# 03_Power.net
KiCad netlist of a schematic drawn in Altium Designer
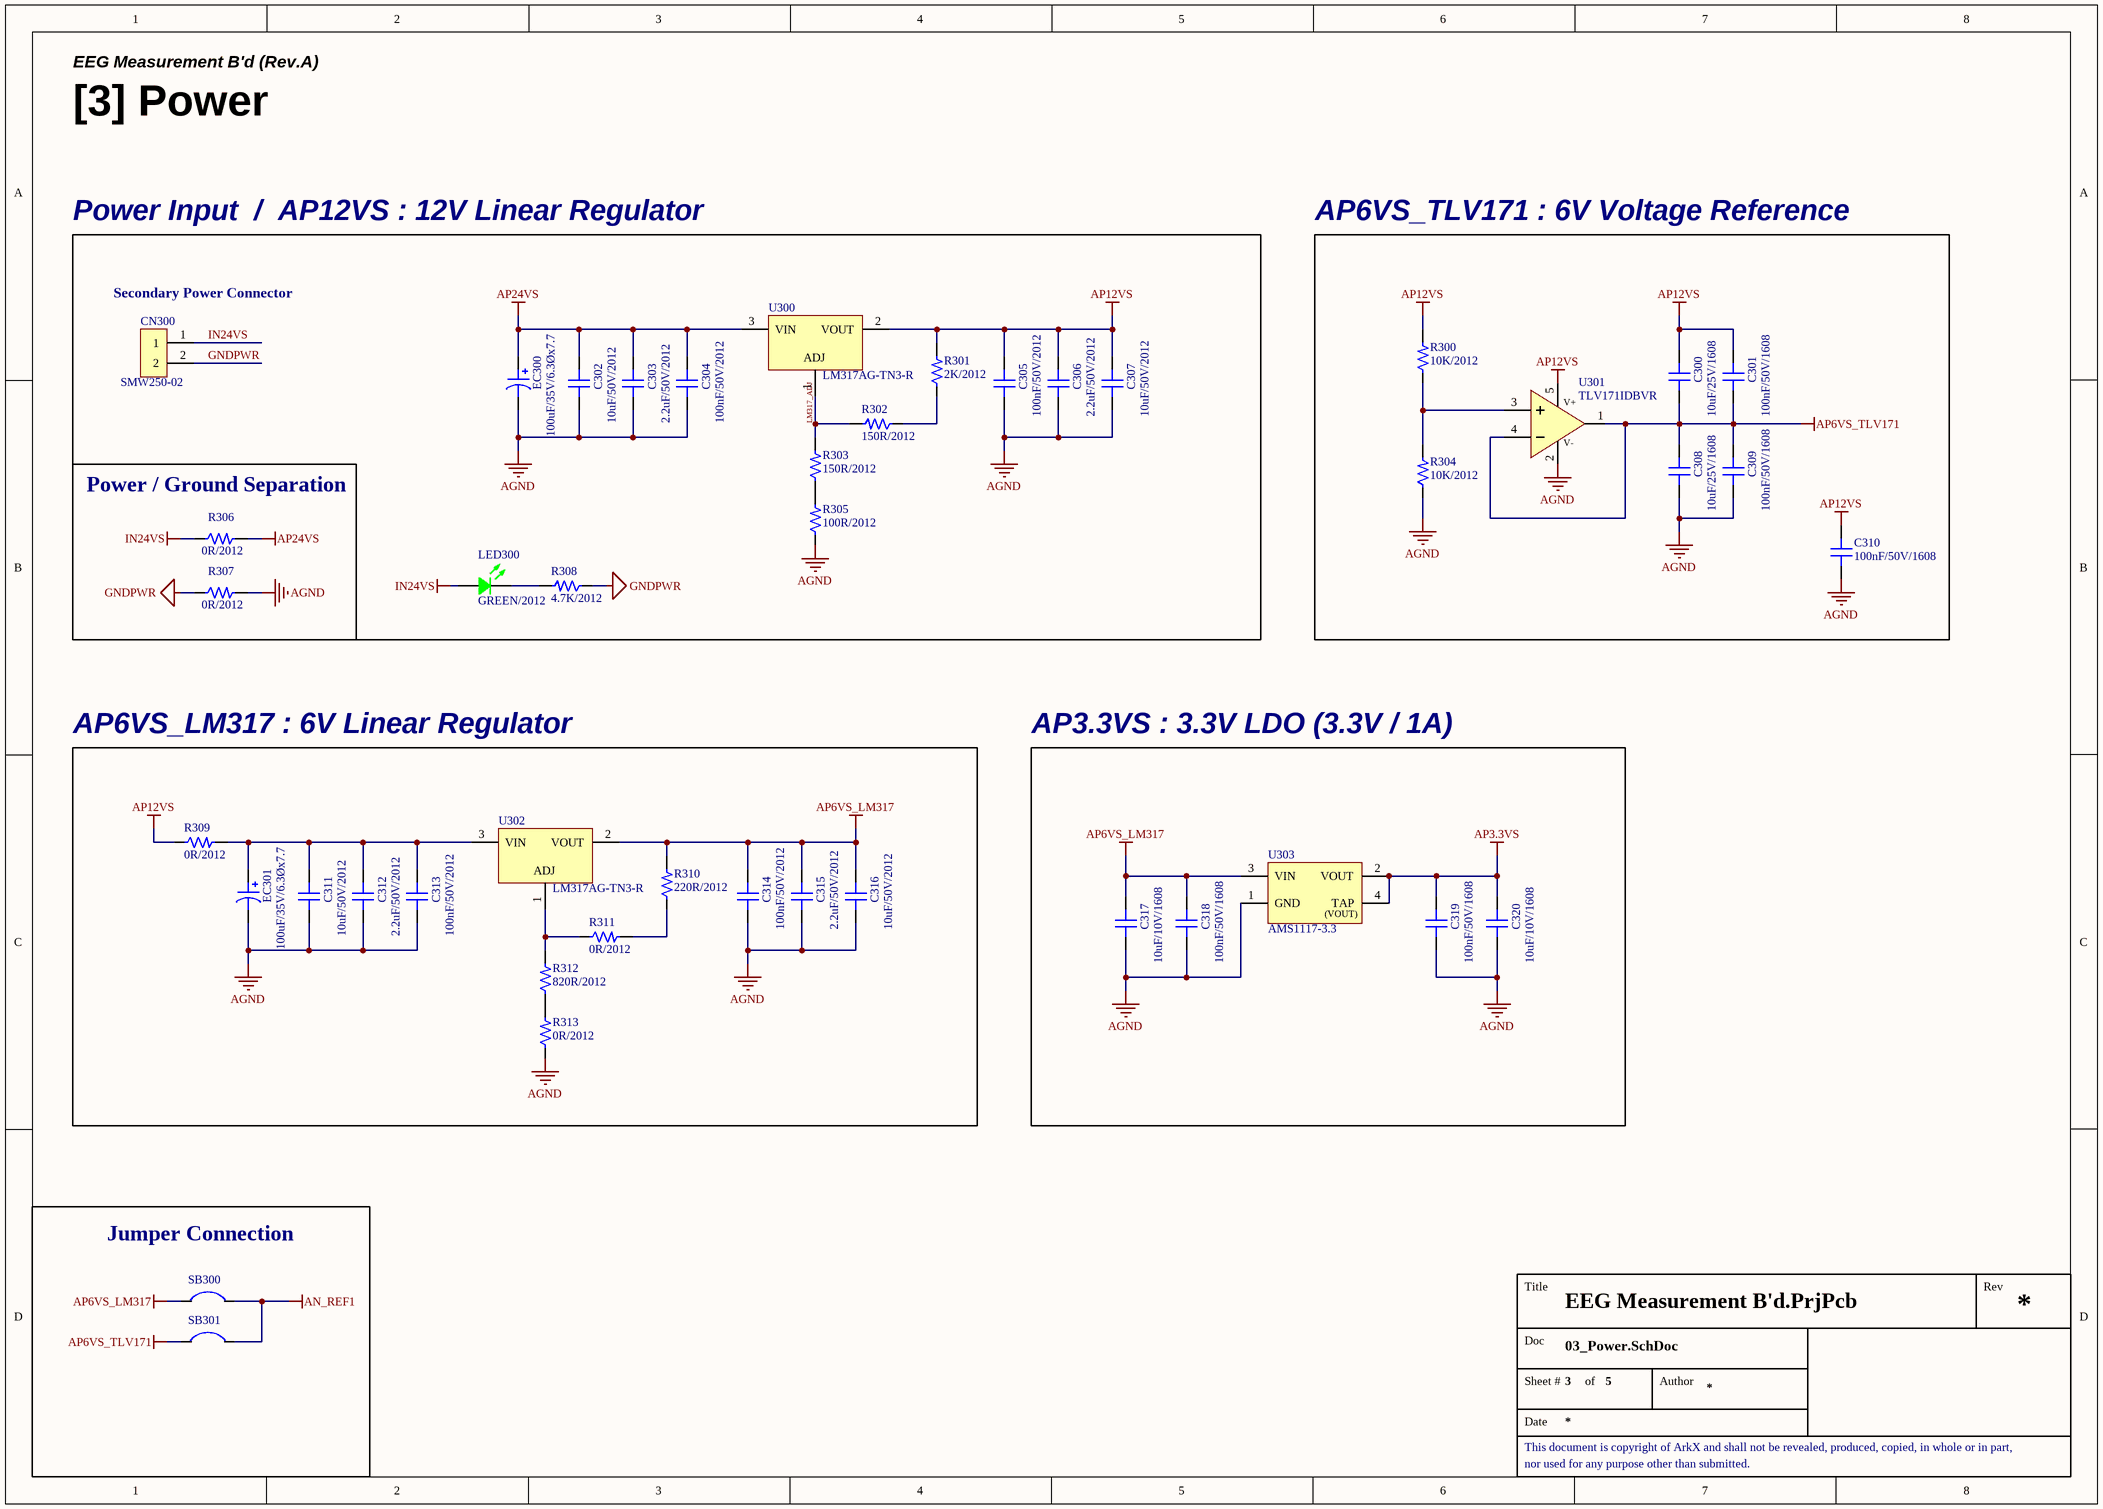
[diagram p0: 03_Power.SchDoc]

(export (version "E")
  (design (tool "Eeschema 10.0.6"))
  (components
    (comp (ref "C300")
      (value "10uF/25V/1608")
      (footprint "CAP 1608 (0603_INCH)")
      (description "Ceramic CAP_10uF/25V/1608")
      (fields (field (name "LCSC PART #") "C96446"))
      (libsource (lib "Arkx") (part "CAP_10uF/25V/1608"))
    )
    (comp (ref "C301")
      (value "100nF/50V/1608")
      (footprint "CAP 1608 (0603_INCH)")
      (description "Ceramic CAP_100nF/50V/1608")
      (fields (field (name "LCSC PART #") "C14663"))
      (libsource (lib "Arkx") (part "CAP_100nF/50V/1608"))
    )
    (comp (ref "C302")
      (value "10uF/50V/2012")
      (footprint "CAP 2012 (0805_INCH)")
      (description "Ceramic CAP_10uF/50V/2012")
      (fields (field (name "LCSC PART #") "C440198"))
      (libsource (lib "Arkx") (part "CAP_10uF/50V/2012"))
    )
    (comp (ref "C303")
      (value "2.2uF/50V/2012")
      (footprint "CAP 2012 (0805_INCH)")
      (description "Ceramic CAP_2.2uF/50V/2012")
      (fields (field (name "LCSC PART #") "C377773"))
      (libsource (lib "Arkx") (part "CAP_2.2uF/50V/2012"))
    )
    (comp (ref "C304")
      (value "100nF/50V/2012")
      (footprint "CAP 2012 (0805_INCH)")
      (description "Ceramic CAP_100nF/50V/2012")
      (fields (field (name "LCSC PART #") "C49678"))
      (libsource (lib "Arkx") (part "CAP_100nF/50V/2012"))
    )
    (comp (ref "C305")
      (value "100nF/50V/2012")
      (footprint "CAP 2012 (0805_INCH)")
      (description "Ceramic CAP_100nF/50V/2012")
      (fields (field (name "LCSC PART #") "C49678"))
      (libsource (lib "Arkx") (part "CAP_100nF/50V/2012"))
    )
    (comp (ref "C306")
      (value "2.2uF/50V/2012")
      (footprint "CAP 2012 (0805_INCH)")
      (description "Ceramic CAP_2.2uF/50V/2012")
      (fields (field (name "LCSC PART #") "C377773"))
      (libsource (lib "Arkx") (part "CAP_2.2uF/50V/2012"))
    )
    (comp (ref "C307")
      (value "10uF/50V/2012")
      (footprint "CAP 2012 (0805_INCH)")
      (description "Ceramic CAP_10uF/50V/2012")
      (fields (field (name "LCSC PART #") "C440198"))
      (libsource (lib "Arkx") (part "CAP_10uF/50V/2012"))
    )
    (comp (ref "C308")
      (value "10uF/25V/1608")
      (footprint "CAP 1608 (0603_INCH)")
      (description "Ceramic CAP_10uF/25V/1608")
      (fields (field (name "LCSC PART #") "C96446"))
      (libsource (lib "Arkx") (part "CAP_10uF/25V/1608"))
    )
    (comp (ref "C309")
      (value "100nF/50V/1608")
      (footprint "CAP 1608 (0603_INCH)")
      (description "Ceramic CAP_100nF/50V/1608")
      (fields (field (name "LCSC PART #") "C14663"))
      (libsource (lib "Arkx") (part "CAP_100nF/50V/1608"))
    )
    (comp (ref "C310")
      (value "100nF/50V/1608")
      (footprint "CAP 1608 (0603_INCH)")
      (description "Ceramic CAP_100nF/50V/1608")
      (fields (field (name "LCSC PART #") "C14663"))
      (libsource (lib "Arkx") (part "CAP_100nF/50V/1608"))
    )
    (comp (ref "C311")
      (value "10uF/50V/2012")
      (footprint "CAP 2012 (0805_INCH)")
      (description "Ceramic CAP_10uF/50V/2012")
      (fields (field (name "LCSC PART #") "C440198"))
      (libsource (lib "Arkx") (part "CAP_10uF/50V/2012"))
    )
    (comp (ref "C312")
      (value "2.2uF/50V/2012")
      (footprint "CAP 2012 (0805_INCH)")
      (description "Ceramic CAP_2.2uF/50V/2012")
      (fields (field (name "LCSC PART #") "C377773"))
      (libsource (lib "Arkx") (part "CAP_2.2uF/50V/2012"))
    )
    (comp (ref "C313")
      (value "100nF/50V/2012")
      (footprint "CAP 2012 (0805_INCH)")
      (description "Ceramic CAP_100nF/50V/2012")
      (fields (field (name "LCSC PART #") "C49678"))
      (libsource (lib "Arkx") (part "CAP_100nF/50V/2012"))
    )
    (comp (ref "C314")
      (value "100nF/50V/2012")
      (footprint "CAP 2012 (0805_INCH)")
      (description "Ceramic CAP_100nF/50V/2012")
      (fields (field (name "LCSC PART #") "C49678"))
      (libsource (lib "Arkx") (part "CAP_100nF/50V/2012"))
    )
    (comp (ref "C315")
      (value "2.2uF/50V/2012")
      (footprint "CAP 2012 (0805_INCH)")
      (description "Ceramic CAP_2.2uF/50V/2012")
      (fields (field (name "LCSC PART #") "C377773"))
      (libsource (lib "Arkx") (part "CAP_2.2uF/50V/2012"))
    )
    (comp (ref "C316")
      (value "10uF/50V/2012")
      (footprint "CAP 2012 (0805_INCH)")
      (description "Ceramic CAP_10uF/50V/2012")
      (fields (field (name "LCSC PART #") "C440198"))
      (libsource (lib "Arkx") (part "CAP_10uF/50V/2012"))
    )
    (comp (ref "C317")
      (value "10uF/10V/1608")
      (footprint "CAP 1608 (0603_INCH)")
      (description "Ceramic CAP_10uF/10V/1608")
      (fields (field (name "LCSC PART #") "C19702"))
      (libsource (lib "Arkx") (part "CAP_10uF/10V/1608"))
    )
    (comp (ref "C318")
      (value "100nF/50V/1608")
      (footprint "CAP 1608 (0603_INCH)")
      (description "Ceramic CAP_100nF/50V/1608")
      (fields (field (name "LCSC PART #") "C14663"))
      (libsource (lib "Arkx") (part "CAP_100nF/50V/1608"))
    )
    (comp (ref "C319")
      (value "100nF/50V/1608")
      (footprint "CAP 1608 (0603_INCH)")
      (description "Ceramic CAP_100nF/50V/1608")
      (fields (field (name "LCSC PART #") "C14663"))
      (libsource (lib "Arkx") (part "CAP_100nF/50V/1608"))
    )
    (comp (ref "C320")
      (value "10uF/10V/1608")
      (footprint "CAP 1608 (0603_INCH)")
      (description "Ceramic CAP_10uF/10V/1608")
      (fields (field (name "LCSC PART #") "C19702"))
      (libsource (lib "Arkx") (part "CAP_10uF/10V/1608"))
    )
    (comp (ref "CN300")
      (value "SMW250-02")
      (footprint "CON_SMW250-02")
      (description "YEONHO 2.5mm Pitch Vertical Connector 2Pin")
      (libsource (lib "Arkx") (part "CON_SMW250-02"))
    )
    (comp (ref "EC300")
      (value "100uF/35V/6.3Øx7.7")
      (footprint "CAP ALSMD 6.6MM H7.7MM")
      (description "Eletrolytic CAP_100uF/35V/6.3Øx7.7")
      (fields (field (name "LCSC PART #") "C176666"))
      (libsource (lib "Arkx") (part "CAP_EC 100uF/35V/6.3Øx7.7"))
    )
    (comp (ref "EC301")
      (value "100uF/35V/6.3Øx7.7")
      (footprint "CAP ALSMD 6.6MM H7.7MM")
      (description "Eletrolytic CAP_100uF/35V/6.3Øx7.7")
      (fields (field (name "LCSC PART #") "C176666"))
      (libsource (lib "Arkx") (part "CAP_EC 100uF/35V/6.3Øx7.7"))
    )
    (comp (ref "LED300")
      (value "GREEN/2012")
      (footprint "LED MHT170RGBCT (GREEN)")
      (fields (field (name "LCSC PART #") "C2962094"))
      (libsource (lib "Arkx") (part "LED_MHT170RGBCT(GREEN)"))
    )
    (comp (ref "R300")
      (value "10K/2012")
      (footprint "RES 2012 (0805_inch)")
      (description "RES_10K/2012/0.125W")
      (fields (field (name "LCSC PART #") "C17414"))
      (libsource (lib "Arkx") (part "RES_10K/2012/0.125W"))
    )
    (comp (ref "R301")
      (value "2K/2012")
      (footprint "RES 2012 (0805_inch)")
      (description "RES_2K/2012/0.125W")
      (fields (field (name "LCSC PART #") "C17604"))
      (libsource (lib "Arkx") (part "RES_2K/2012/0.125W"))
    )
    (comp (ref "R302")
      (value "150R/2012")
      (footprint "RES 2012 (0805_inch)")
      (description "RES_150R/2012/0.125W")
      (fields (field (name "LCSC PART #") "C17471"))
      (libsource (lib "Arkx") (part "RES_150R/2012/0.125W"))
    )
    (comp (ref "R303")
      (value "150R/2012")
      (footprint "RES 2012 (0805_inch)")
      (description "RES_150R/2012/0.125W")
      (fields (field (name "LCSC PART #") "C17471"))
      (libsource (lib "Arkx") (part "RES_150R/2012/0.125W"))
    )
    (comp (ref "R304")
      (value "10K/2012")
      (footprint "RES 2012 (0805_inch)")
      (description "RES_10K/2012/0.125W")
      (fields (field (name "LCSC PART #") "C17414"))
      (libsource (lib "Arkx") (part "RES_10K/2012/0.125W"))
    )
    (comp (ref "R305")
      (value "100R/2012")
      (footprint "RES 2012 (0805_inch)")
      (description "RES_100R/2012/0.125W")
      (fields (field (name "LCSC PART #") "C17408"))
      (libsource (lib "Arkx") (part "RES_100R/2012/0.125W"))
    )
    (comp (ref "R306")
      (value "0R/2012")
      (footprint "RES 2012 (0805_inch)")
      (description "RES_0R/2012/0.125W")
      (fields (field (name "LCSC PART #") "C17477"))
      (libsource (lib "Arkx") (part "RES_0R/2012/0.125W"))
    )
    (comp (ref "R307")
      (value "0R/2012")
      (footprint "RES 2012 (0805_inch)")
      (description "RES_0R/2012/0.125W")
      (fields (field (name "LCSC PART #") "C17477"))
      (libsource (lib "Arkx") (part "RES_0R/2012/0.125W"))
    )
    (comp (ref "R308")
      (value "4.7K/2012")
      (footprint "RES 2012 (0805_inch)")
      (description "RES_4.7K/2012/0.125W")
      (fields (field (name "LCSC PART #") "C17673"))
      (libsource (lib "Arkx") (part "RES_4.7K/2012/0.125W"))
    )
    (comp (ref "R309")
      (value "0R/2012")
      (footprint "RES 2012 (0805_inch)")
      (description "RES_0R/2012/0.125W")
      (fields (field (name "LCSC PART #") "C17477"))
      (libsource (lib "Arkx") (part "RES_0R/2012/0.125W"))
    )
    (comp (ref "R310")
      (value "220R/2012")
      (footprint "RES 2012 (0805_inch)")
      (description "RES_220R/2012/0.125W")
      (fields (field (name "LCSC PART #") "C17557"))
      (libsource (lib "Arkx") (part "RES_220R/2012/0.125W"))
    )
    (comp (ref "R311")
      (value "0R/2012")
      (footprint "RES 2012 (0805_inch)")
      (description "RES_0R/2012/0.125W")
      (fields (field (name "LCSC PART #") "C17477"))
      (libsource (lib "Arkx") (part "RES_0R/2012/0.125W"))
    )
    (comp (ref "R312")
      (value "820R/2012")
      (footprint "RES 2012 (0805_inch)")
      (description "RES_820R/2012/0.125W")
      (fields (field (name "LCSC PART #") "C17837"))
      (libsource (lib "Arkx") (part "RES_820R/2012/0.125W"))
    )
    (comp (ref "R313")
      (value "0R/2012")
      (footprint "RES 2012 (0805_inch)")
      (description "RES_0R/2012/0.125W")
      (fields (field (name "LCSC PART #") "C17477"))
      (libsource (lib "Arkx") (part "RES_0R/2012/0.125W"))
    )
    (comp (ref "SB300")
      (value "SB")
      (footprint "SB (Solder-Bridge)")
      (description "SB_Solder-Bridge")
      (libsource (lib "Arkx") (part "SB_Solder-Bridge"))
    )
    (comp (ref "SB301")
      (value "SB")
      (footprint "SB (Solder-Bridge)")
      (description "SB_Solder-Bridge")
      (libsource (lib "Arkx") (part "SB_Solder-Bridge"))
    )
    (comp (ref "U300")
      (value "LM317AG-TN3-R")
      (footprint "IC_TO-252-2(DPAK)")
      (fields (field (name "LCSC PART #") "C75510"))
      (libsource (lib "Arkx") (part "IC_REG_LM317AG-TN3-R"))
    )
    (comp (ref "U301")
      (value "TLV171IDBVR")
      (footprint "SOT-23-5 (TI DBV PACKAGE)")
      (description "Single, 36-V, 3-MHz, low-power operational amplifier for cost-sensitive applications")
      (fields (field (name "LCSC PART #") "C2864299"))
      (libsource (lib "Arkx") (part "IC_OPAMP_TLV171IDBVR"))
    )
    (comp (ref "U302")
      (value "LM317AG-TN3-R")
      (footprint "IC_TO-252-2(DPAK)")
      (fields (field (name "LCSC PART #") "C75510"))
      (libsource (lib "Arkx") (part "IC_REG_LM317AG-TN3-R"))
    )
    (comp (ref "U303")
      (value "AMS1117-3.3")
      (footprint "SOT 223-3 (DIODES INCORPORATED)")
      (fields (field (name "LCSC PART #") "C6186"))
      (libsource (lib "Arkx") (part "IC_REG_AMS1117-3.3"))
    )
  )
  (nets
    (net (code "1") (name "/LM317_ADJ") (class "Default")
      (node (ref "R302") (pin "2") (pinfunction "2_2") (pintype "passive"))
      (node (ref "R303") (pin "2") (pinfunction "2_2") (pintype "passive"))
      (node (ref "U300") (pin "1") (pinfunction "ADJ_1") (pintype "passive"))
    )
    (net (code "2") (name "AGND") (class "Default")
      (node (ref "C302") (pin "1") (pinfunction "1_1") (pintype "passive"))
      (node (ref "C303") (pin "1") (pinfunction "1_1") (pintype "passive"))
      (node (ref "C304") (pin "1") (pinfunction "1_1") (pintype "passive"))
      (node (ref "C305") (pin "1") (pinfunction "1_1") (pintype "passive"))
      (node (ref "C306") (pin "1") (pinfunction "1_1") (pintype "passive"))
      (node (ref "C307") (pin "1") (pinfunction "1_1") (pintype "passive"))
      (node (ref "C308") (pin "1") (pinfunction "1_1") (pintype "passive"))
      (node (ref "C309") (pin "1") (pinfunction "1_1") (pintype "passive"))
      (node (ref "C310") (pin "1") (pinfunction "1_1") (pintype "passive"))
      (node (ref "C311") (pin "1") (pinfunction "1_1") (pintype "passive"))
      (node (ref "C312") (pin "1") (pinfunction "1_1") (pintype "passive"))
      (node (ref "C313") (pin "1") (pinfunction "1_1") (pintype "passive"))
      (node (ref "C314") (pin "1") (pinfunction "1_1") (pintype "passive"))
      (node (ref "C315") (pin "1") (pinfunction "1_1") (pintype "passive"))
      (node (ref "C316") (pin "1") (pinfunction "1_1") (pintype "passive"))
      (node (ref "C317") (pin "1") (pinfunction "1_1") (pintype "passive"))
      (node (ref "C318") (pin "1") (pinfunction "1_1") (pintype "passive"))
      (node (ref "C319") (pin "1") (pinfunction "1_1") (pintype "passive"))
      (node (ref "C320") (pin "1") (pinfunction "1_1") (pintype "passive"))
      (node (ref "EC300") (pin "2") (pinfunction "2_2") (pintype "passive"))
      (node (ref "EC301") (pin "2") (pinfunction "2_2") (pintype "passive"))
      (node (ref "R304") (pin "1") (pinfunction "1_1") (pintype "passive"))
      (node (ref "R305") (pin "1") (pinfunction "1_1") (pintype "passive"))
      (node (ref "R307") (pin "2") (pinfunction "2_2") (pintype "passive"))
      (node (ref "R313") (pin "1") (pinfunction "1_1") (pintype "passive"))
      (node (ref "U301") (pin "2") (pinfunction "V-_2") (pintype "passive"))
      (node (ref "U303") (pin "1") (pinfunction "GND_1") (pintype "passive"))
    )
    (net (code "3") (name "AN_REF1") (class "Default")
      (node (ref "SB300") (pin "1") (pinfunction "1_1") (pintype "passive"))
      (node (ref "SB301") (pin "1") (pinfunction "1_1") (pintype "passive"))
    )
    (net (code "4") (name "AP3.3VS") (class "Default")
      (node (ref "C319") (pin "2") (pinfunction "2_2") (pintype "passive"))
      (node (ref "C320") (pin "2") (pinfunction "2_2") (pintype "passive"))
      (node (ref "U303") (pin "2") (pinfunction "VOUT_2") (pintype "passive"))
      (node (ref "U303") (pin "4") (pinfunction "TAP_4") (pintype "passive"))
    )
    (net (code "5") (name "AP6VS_LM317") (class "Default")
      (node (ref "C314") (pin "2") (pinfunction "2_2") (pintype "passive"))
      (node (ref "C315") (pin "2") (pinfunction "2_2") (pintype "passive"))
      (node (ref "C316") (pin "2") (pinfunction "2_2") (pintype "passive"))
      (node (ref "C317") (pin "2") (pinfunction "2_2") (pintype "passive"))
      (node (ref "C318") (pin "2") (pinfunction "2_2") (pintype "passive"))
      (node (ref "R310") (pin "2") (pinfunction "2_2") (pintype "passive"))
      (node (ref "SB300") (pin "2") (pinfunction "2_2") (pintype "passive"))
      (node (ref "U302") (pin "2") (pinfunction "VOUT_2") (pintype "passive"))
      (node (ref "U303") (pin "3") (pinfunction "VIN_3") (pintype "passive"))
    )
    (net (code "6") (name "AP6VS_TLV171") (class "Default")
      (node (ref "C300") (pin "1") (pinfunction "1_1") (pintype "passive"))
      (node (ref "C301") (pin "1") (pinfunction "1_1") (pintype "passive"))
      (node (ref "C308") (pin "2") (pinfunction "2_2") (pintype "passive"))
      (node (ref "C309") (pin "2") (pinfunction "2_2") (pintype "passive"))
      (node (ref "SB301") (pin "2") (pinfunction "2_2") (pintype "passive"))
      (node (ref "U301") (pin "1") (pinfunction "OUT_1") (pintype "passive"))
      (node (ref "U301") (pin "4") (pinfunction "IN-_4") (pintype "passive"))
    )
    (net (code "7") (name "AP12VS") (class "Default")
      (node (ref "C300") (pin "2") (pinfunction "2_2") (pintype "passive"))
      (node (ref "C301") (pin "2") (pinfunction "2_2") (pintype "passive"))
      (node (ref "C305") (pin "2") (pinfunction "2_2") (pintype "passive"))
      (node (ref "C306") (pin "2") (pinfunction "2_2") (pintype "passive"))
      (node (ref "C307") (pin "2") (pinfunction "2_2") (pintype "passive"))
      (node (ref "C310") (pin "2") (pinfunction "2_2") (pintype "passive"))
      (node (ref "R300") (pin "2") (pinfunction "2_2") (pintype "passive"))
      (node (ref "R301") (pin "2") (pinfunction "2_2") (pintype "passive"))
      (node (ref "R309") (pin "1") (pinfunction "1_1") (pintype "passive"))
      (node (ref "U300") (pin "2") (pinfunction "VOUT_2") (pintype "passive"))
      (node (ref "U301") (pin "5") (pinfunction "V+_5") (pintype "passive"))
    )
    (net (code "8") (name "AP24VS") (class "Default")
      (node (ref "C302") (pin "2") (pinfunction "2_2") (pintype "passive"))
      (node (ref "C303") (pin "2") (pinfunction "2_2") (pintype "passive"))
      (node (ref "C304") (pin "2") (pinfunction "2_2") (pintype "passive"))
      (node (ref "EC300") (pin "1") (pinfunction "1_1") (pintype "passive"))
      (node (ref "R306") (pin "2") (pinfunction "2_2") (pintype "passive"))
      (node (ref "U300") (pin "3") (pinfunction "VIN_3") (pintype "passive"))
    )
    (net (code "9") (name "GNDPWR") (class "Default")
      (node (ref "CN300") (pin "2") (pinfunction "2_2") (pintype "passive"))
      (node (ref "R307") (pin "1") (pinfunction "1_1") (pintype "passive"))
      (node (ref "R308") (pin "1") (pinfunction "1_1") (pintype "passive"))
    )
    (net (code "10") (name "IN24VS") (class "Default")
      (node (ref "CN300") (pin "1") (pinfunction "1_1") (pintype "passive"))
      (node (ref "LED300") (pin "4") (pinfunction "Common_Anode_4") (pintype "passive"))
      (node (ref "R306") (pin "1") (pinfunction "1_1") (pintype "passive"))
    )
    (net (code "11") (name "Net-(LED300-GREEN)") (class "Default")
      (node (ref "LED300") (pin "2") (pinfunction "GREEN_2") (pintype "passive"))
      (node (ref "R308") (pin "2") (pinfunction "2_2") (pintype "passive"))
    )
    (net (code "12") (name "Net-(R301-Pad1)") (class "Default")
      (node (ref "R301") (pin "1") (pinfunction "1_1") (pintype "passive"))
      (node (ref "R302") (pin "1") (pinfunction "1_1") (pintype "passive"))
    )
    (net (code "13") (name "Net-(R303-Pad1)") (class "Default")
      (node (ref "R303") (pin "1") (pinfunction "1_1") (pintype "passive"))
      (node (ref "R305") (pin "2") (pinfunction "2_2") (pintype "passive"))
    )
    (net (code "14") (name "Net-(R310-Pad1)") (class "Default")
      (node (ref "R310") (pin "1") (pinfunction "1_1") (pintype "passive"))
      (node (ref "R311") (pin "2") (pinfunction "2_2") (pintype "passive"))
    )
    (net (code "15") (name "Net-(R312-Pad1)") (class "Default")
      (node (ref "R312") (pin "1") (pinfunction "1_1") (pintype "passive"))
      (node (ref "R313") (pin "2") (pinfunction "2_2") (pintype "passive"))
    )
    (net (code "16") (name "Net-(U301-IN+)") (class "Default")
      (node (ref "R300") (pin "1") (pinfunction "1_1") (pintype "passive"))
      (node (ref "R304") (pin "2") (pinfunction "2_2") (pintype "passive"))
      (node (ref "U301") (pin "3") (pinfunction "IN+_3") (pintype "passive"))
    )
    (net (code "17") (name "Net-(U302-ADJ)") (class "Default")
      (node (ref "R311") (pin "1") (pinfunction "1_1") (pintype "passive"))
      (node (ref "R312") (pin "2") (pinfunction "2_2") (pintype "passive"))
      (node (ref "U302") (pin "1") (pinfunction "ADJ_1") (pintype "passive"))
    )
    (net (code "18") (name "Net-(U302-VIN)") (class "Default")
      (node (ref "C311") (pin "2") (pinfunction "2_2") (pintype "passive"))
      (node (ref "C312") (pin "2") (pinfunction "2_2") (pintype "passive"))
      (node (ref "C313") (pin "2") (pinfunction "2_2") (pintype "passive"))
      (node (ref "EC301") (pin "1") (pinfunction "1_1") (pintype "passive"))
      (node (ref "R309") (pin "2") (pinfunction "2_2") (pintype "passive"))
      (node (ref "U302") (pin "3") (pinfunction "VIN_3") (pintype "passive"))
    )
  )
)
